# Nucleo.net
KiCad netlist of a schematic drawn in Altium Designer
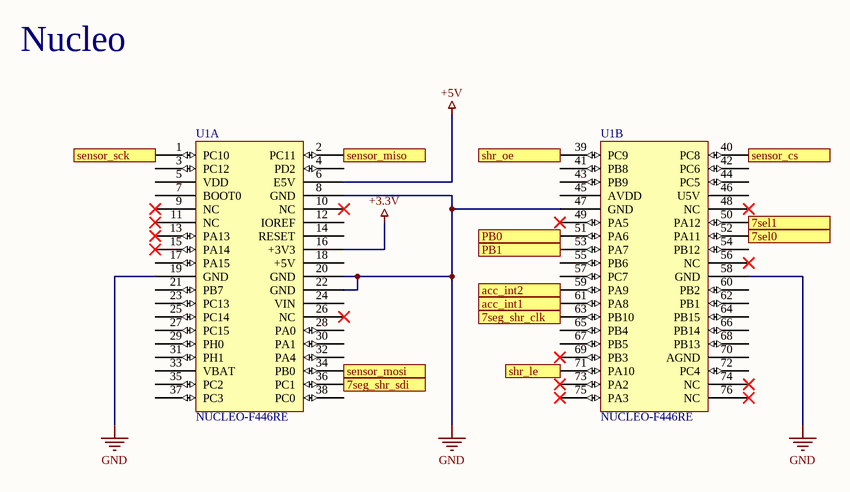
[diagram p0: Nucleo.SchDoc]

(export (version "E")
  (design (tool "Eeschema 10.0.6"))
  (components
    (comp (ref "U1")
      (value "NUCLEO-F446RE")
      (footprint "FP_NUCLEO-64")
      (libsource (lib "hallglib") (part "NUCLEO-F446RE"))
    )
  )
  (nets
    (net (code "1") (name "+3.3V") (class "Default")
      (node (ref "U1") (pin "16") (pinfunction "+3V3_16") (pintype "power_in"))
    )
    (net (code "2") (name "+5V") (class "Default")
      (node (ref "U1") (pin "6") (pinfunction "E5V_6") (pintype "power_in"))
    )
    (net (code "3") (name "/7seg_shr_clk") (class "Default")
      (node (ref "U1") (pin "63") (pinfunction "PB10_63") (pintype "bidirectional"))
    )
    (net (code "4") (name "/7seg_shr_sdi") (class "Default")
      (node (ref "U1") (pin "36") (pinfunction "PC1_36") (pintype "bidirectional"))
    )
    (net (code "5") (name "/7sel0") (class "Default")
      (node (ref "U1") (pin "52") (pinfunction "PA11_52") (pintype "bidirectional"))
    )
    (net (code "6") (name "/7sel1") (class "Default")
      (node (ref "U1") (pin "50") (pinfunction "PA12_50") (pintype "bidirectional"))
    )
    (net (code "7") (name "/PB0") (class "Default")
      (node (ref "U1") (pin "51") (pinfunction "PA6_51") (pintype "bidirectional"))
    )
    (net (code "8") (name "/PB1") (class "Default")
      (node (ref "U1") (pin "53") (pinfunction "PA7_53") (pintype "bidirectional"))
    )
    (net (code "9") (name "/acc_int1") (class "Default")
      (node (ref "U1") (pin "61") (pinfunction "PA8_61") (pintype "bidirectional"))
    )
    (net (code "10") (name "/acc_int2") (class "Default")
      (node (ref "U1") (pin "59") (pinfunction "PA9_59") (pintype "bidirectional"))
    )
    (net (code "11") (name "/sensor_cs") (class "Default")
      (node (ref "U1") (pin "40") (pinfunction "PC8_40") (pintype "bidirectional"))
    )
    (net (code "12") (name "/sensor_miso") (class "Default")
      (node (ref "U1") (pin "2") (pinfunction "PC11_2") (pintype "bidirectional"))
    )
    (net (code "13") (name "/sensor_mosi") (class "Default")
      (node (ref "U1") (pin "34") (pinfunction "PB0_34") (pintype "bidirectional"))
    )
    (net (code "14") (name "/sensor_sck") (class "Default")
      (node (ref "U1") (pin "1") (pinfunction "PC10_1") (pintype "bidirectional"))
    )
    (net (code "15") (name "/shr_le") (class "Default")
      (node (ref "U1") (pin "71") (pinfunction "PA10_71") (pintype "bidirectional"))
    )
    (net (code "16") (name "/shr_oe") (class "Default")
      (node (ref "U1") (pin "39") (pinfunction "PC9_39") (pintype "bidirectional"))
    )
    (net (code "17") (name "GND") (class "Default")
      (node (ref "U1") (pin "19") (pinfunction "GND_19") (pintype "passive"))
      (node (ref "U1") (pin "20") (pinfunction "GND_20") (pintype "passive"))
      (node (ref "U1") (pin "22") (pinfunction "GND_22") (pintype "passive"))
      (node (ref "U1") (pin "47") (pinfunction "GND_47") (pintype "passive"))
      (node (ref "U1") (pin "58") (pinfunction "GND_58") (pintype "passive"))
      (node (ref "U1") (pin "8") (pinfunction "GND_8") (pintype "passive"))
    )
    (net (code "18") (name "unconnected-(U1A-+5V-Pad18)") (class "Default")
      (node (ref "U1") (pin "18") (pinfunction "+5V_18") (pintype "power_in"))
    )
    (net (code "19") (name "unconnected-(U1A-BOOT0-Pad7)") (class "Default")
      (node (ref "U1") (pin "7") (pinfunction "BOOT0_7") (pintype "passive"))
    )
    (net (code "20") (name "unconnected-(U1A-IOREF-Pad12)") (class "Default")
      (node (ref "U1") (pin "12") (pinfunction "IOREF_12") (pintype "passive"))
    )
    (net (code "21") (name "unconnected-(U1A-NC-Pad9)") (class "Default")
      (node (ref "U1") (pin "9") (pinfunction "NC_9") (pintype "passive+no_connect"))
    )
    (net (code "22") (name "unconnected-(U1A-NC-Pad10)") (class "Default")
      (node (ref "U1") (pin "10") (pinfunction "NC_10") (pintype "passive+no_connect"))
    )
    (net (code "23") (name "unconnected-(U1A-NC-Pad11)") (class "Default")
      (node (ref "U1") (pin "11") (pinfunction "NC_11") (pintype "passive+no_connect"))
    )
    (net (code "24") (name "unconnected-(U1A-NC-Pad26)") (class "Default")
      (node (ref "U1") (pin "26") (pinfunction "NC_26") (pintype "passive+no_connect"))
    )
    (net (code "25") (name "unconnected-(U1A-PA0-Pad28)") (class "Default")
      (node (ref "U1") (pin "28") (pinfunction "PA0_28") (pintype "bidirectional"))
    )
    (net (code "26") (name "unconnected-(U1A-PA1-Pad30)") (class "Default")
      (node (ref "U1") (pin "30") (pinfunction "PA1_30") (pintype "bidirectional"))
    )
    (net (code "27") (name "unconnected-(U1A-PA4-Pad32)") (class "Default")
      (node (ref "U1") (pin "32") (pinfunction "PA4_32") (pintype "bidirectional"))
    )
    (net (code "28") (name "unconnected-(U1A-PA13-Pad13)") (class "Default")
      (node (ref "U1") (pin "13") (pinfunction "PA13_13") (pintype "bidirectional+no_connect"))
    )
    (net (code "29") (name "unconnected-(U1A-PA14-Pad15)") (class "Default")
      (node (ref "U1") (pin "15") (pinfunction "PA14_15") (pintype "bidirectional+no_connect"))
    )
    (net (code "30") (name "unconnected-(U1A-PA15-Pad17)") (class "Default")
      (node (ref "U1") (pin "17") (pinfunction "PA15_17") (pintype "bidirectional"))
    )
    (net (code "31") (name "unconnected-(U1A-PB7-Pad21)") (class "Default")
      (node (ref "U1") (pin "21") (pinfunction "PB7_21") (pintype "bidirectional"))
    )
    (net (code "32") (name "unconnected-(U1A-PC0-Pad38)") (class "Default")
      (node (ref "U1") (pin "38") (pinfunction "PC0_38") (pintype "bidirectional"))
    )
    (net (code "33") (name "unconnected-(U1A-PC2-Pad35)") (class "Default")
      (node (ref "U1") (pin "35") (pinfunction "PC2_35") (pintype "bidirectional"))
    )
    (net (code "34") (name "unconnected-(U1A-PC3-Pad37)") (class "Default")
      (node (ref "U1") (pin "37") (pinfunction "PC3_37") (pintype "bidirectional"))
    )
    (net (code "35") (name "unconnected-(U1A-PC12-Pad3)") (class "Default")
      (node (ref "U1") (pin "3") (pinfunction "PC12_3") (pintype "bidirectional"))
    )
    (net (code "36") (name "unconnected-(U1A-PC13-Pad23)") (class "Default")
      (node (ref "U1") (pin "23") (pinfunction "PC13_23") (pintype "bidirectional"))
    )
    (net (code "37") (name "unconnected-(U1A-PC14-Pad25)") (class "Default")
      (node (ref "U1") (pin "25") (pinfunction "PC14_25") (pintype "bidirectional"))
    )
    (net (code "38") (name "unconnected-(U1A-PC15-Pad27)") (class "Default")
      (node (ref "U1") (pin "27") (pinfunction "PC15_27") (pintype "bidirectional"))
    )
    (net (code "39") (name "unconnected-(U1A-PD2-Pad4)") (class "Default")
      (node (ref "U1") (pin "4") (pinfunction "PD2_4") (pintype "bidirectional"))
    )
    (net (code "40") (name "unconnected-(U1A-PH0-Pad29)") (class "Default")
      (node (ref "U1") (pin "29") (pinfunction "PH0_29") (pintype "bidirectional"))
    )
    (net (code "41") (name "unconnected-(U1A-PH1-Pad31)") (class "Default")
      (node (ref "U1") (pin "31") (pinfunction "PH1_31") (pintype "bidirectional"))
    )
    (net (code "42") (name "unconnected-(U1A-RESET-Pad14)") (class "Default")
      (node (ref "U1") (pin "14") (pinfunction "RESET_14") (pintype "passive"))
    )
    (net (code "43") (name "unconnected-(U1A-VBAT-Pad33)") (class "Default")
      (node (ref "U1") (pin "33") (pinfunction "VBAT_33") (pintype "power_in"))
    )
    (net (code "44") (name "unconnected-(U1A-VDD-Pad5)") (class "Default")
      (node (ref "U1") (pin "5") (pinfunction "VDD_5") (pintype "power_in"))
    )
    (net (code "45") (name "unconnected-(U1A-VIN-Pad24)") (class "Default")
      (node (ref "U1") (pin "24") (pinfunction "VIN_24") (pintype "power_in"))
    )
    (net (code "46") (name "unconnected-(U1B-AGND-Pad70)") (class "Default")
      (node (ref "U1") (pin "70") (pinfunction "AGND_70") (pintype "passive"))
    )
    (net (code "47") (name "unconnected-(U1B-AVDD-Pad45)") (class "Default")
      (node (ref "U1") (pin "45") (pinfunction "AVDD_45") (pintype "power_in"))
    )
    (net (code "48") (name "unconnected-(U1B-NC-Pad48)") (class "Default")
      (node (ref "U1") (pin "48") (pinfunction "NC_48") (pintype "passive+no_connect"))
    )
    (net (code "49") (name "unconnected-(U1B-NC-Pad56)") (class "Default")
      (node (ref "U1") (pin "56") (pinfunction "NC_56") (pintype "passive+no_connect"))
    )
    (net (code "50") (name "unconnected-(U1B-NC-Pad74)") (class "Default")
      (node (ref "U1") (pin "74") (pinfunction "NC_74") (pintype "passive+no_connect"))
    )
    (net (code "51") (name "unconnected-(U1B-NC-Pad76)") (class "Default")
      (node (ref "U1") (pin "76") (pinfunction "NC_76") (pintype "passive+no_connect"))
    )
    (net (code "52") (name "unconnected-(U1B-PA2-Pad73)") (class "Default")
      (node (ref "U1") (pin "73") (pinfunction "PA2_73") (pintype "bidirectional+no_connect"))
    )
    (net (code "53") (name "unconnected-(U1B-PA3-Pad75)") (class "Default")
      (node (ref "U1") (pin "75") (pinfunction "PA3_75") (pintype "bidirectional+no_connect"))
    )
    (net (code "54") (name "unconnected-(U1B-PA5-Pad49)") (class "Default")
      (node (ref "U1") (pin "49") (pinfunction "PA5_49") (pintype "bidirectional+no_connect"))
    )
    (net (code "55") (name "unconnected-(U1B-PB1-Pad62)") (class "Default")
      (node (ref "U1") (pin "62") (pinfunction "PB1_62") (pintype "bidirectional"))
    )
    (net (code "56") (name "unconnected-(U1B-PB2-Pad60)") (class "Default")
      (node (ref "U1") (pin "60") (pinfunction "PB2_60") (pintype "bidirectional"))
    )
    (net (code "57") (name "unconnected-(U1B-PB3-Pad69)") (class "Default")
      (node (ref "U1") (pin "69") (pinfunction "PB3_69") (pintype "bidirectional+no_connect"))
    )
    (net (code "58") (name "unconnected-(U1B-PB4-Pad65)") (class "Default")
      (node (ref "U1") (pin "65") (pinfunction "PB4_65") (pintype "bidirectional"))
    )
    (net (code "59") (name "unconnected-(U1B-PB5-Pad67)") (class "Default")
      (node (ref "U1") (pin "67") (pinfunction "PB5_67") (pintype "bidirectional"))
    )
    (net (code "60") (name "unconnected-(U1B-PB6-Pad55)") (class "Default")
      (node (ref "U1") (pin "55") (pinfunction "PB6_55") (pintype "bidirectional"))
    )
    (net (code "61") (name "unconnected-(U1B-PB8-Pad41)") (class "Default")
      (node (ref "U1") (pin "41") (pinfunction "PB8_41") (pintype "bidirectional"))
    )
    (net (code "62") (name "unconnected-(U1B-PB9-Pad43)") (class "Default")
      (node (ref "U1") (pin "43") (pinfunction "PB9_43") (pintype "bidirectional"))
    )
    (net (code "63") (name "unconnected-(U1B-PB12-Pad54)") (class "Default")
      (node (ref "U1") (pin "54") (pinfunction "PB12_54") (pintype "bidirectional"))
    )
    (net (code "64") (name "unconnected-(U1B-PB13-Pad68)") (class "Default")
      (node (ref "U1") (pin "68") (pinfunction "PB13_68") (pintype "bidirectional"))
    )
    (net (code "65") (name "unconnected-(U1B-PB14-Pad66)") (class "Default")
      (node (ref "U1") (pin "66") (pinfunction "PB14_66") (pintype "bidirectional"))
    )
    (net (code "66") (name "unconnected-(U1B-PB15-Pad64)") (class "Default")
      (node (ref "U1") (pin "64") (pinfunction "PB15_64") (pintype "bidirectional"))
    )
    (net (code "67") (name "unconnected-(U1B-PC4-Pad72)") (class "Default")
      (node (ref "U1") (pin "72") (pinfunction "PC4_72") (pintype "bidirectional"))
    )
    (net (code "68") (name "unconnected-(U1B-PC5-Pad44)") (class "Default")
      (node (ref "U1") (pin "44") (pinfunction "PC5_44") (pintype "bidirectional"))
    )
    (net (code "69") (name "unconnected-(U1B-PC6-Pad42)") (class "Default")
      (node (ref "U1") (pin "42") (pinfunction "PC6_42") (pintype "bidirectional"))
    )
    (net (code "70") (name "unconnected-(U1B-PC7-Pad57)") (class "Default")
      (node (ref "U1") (pin "57") (pinfunction "PC7_57") (pintype "bidirectional"))
    )
    (net (code "71") (name "unconnected-(U1B-U5V-Pad46)") (class "Default")
      (node (ref "U1") (pin "46") (pinfunction "U5V_46") (pintype "power_in"))
    )
  )
)
